# C1G14_VCO_V5.net
KiCad netlist of a schematic drawn in EAGLE
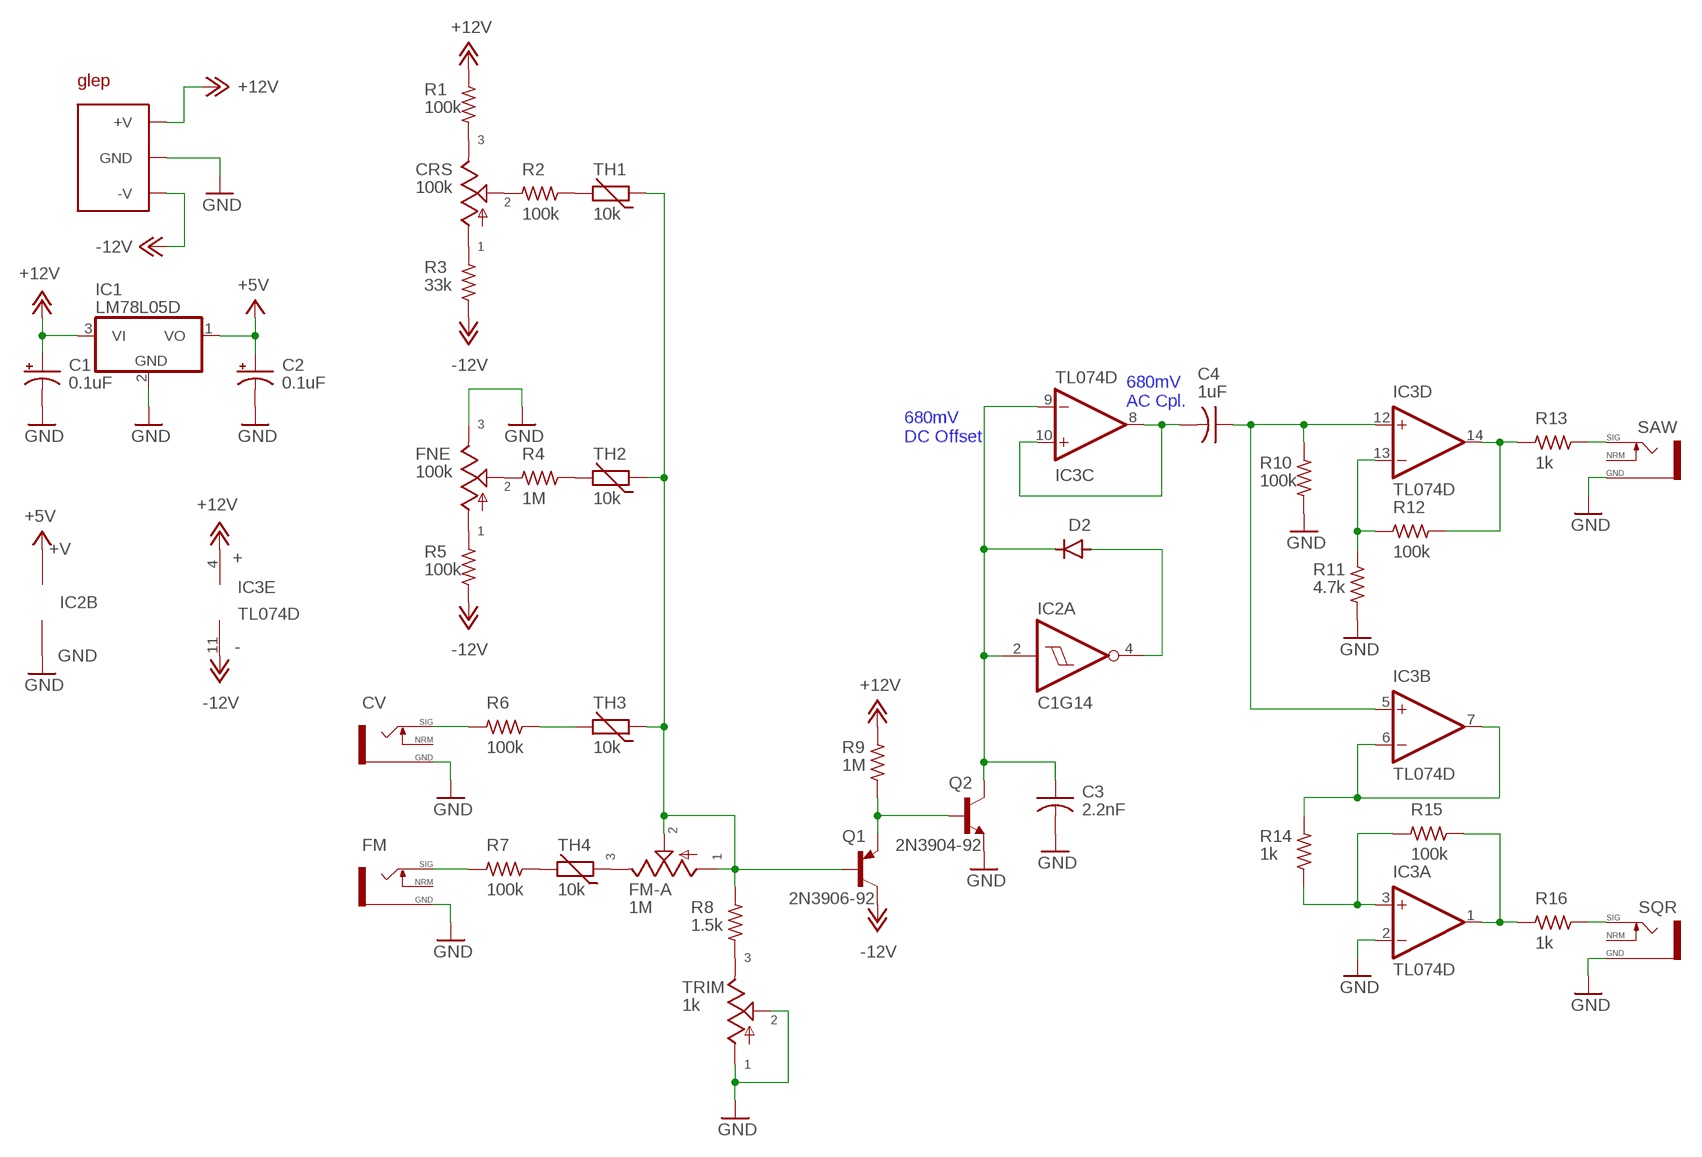
[diagram p0: schematic, sheet 1]

(export (version "E")
  (design (tool "Eeschema 10.0.6"))
  (components
    (comp (ref "C1")
      (value "0.1uF")
      (footprint "eagle-import:E025")
      (libsource (lib "eagle-import") (part "CPOL-E025"))
    )
    (comp (ref "C2")
      (value "0.1uF")
      (footprint "eagle-import:E025")
      (libsource (lib "eagle-import") (part "CPOL-E025"))
    )
    (comp (ref "C3")
      (value "2.2nF")
      (footprint "eagle-import:C05")
      (libsource (lib "eagle-import") (part "C-05"))
    )
    (comp (ref "C4")
      (value "1uF")
      (footprint "eagle-import:C05")
      (libsource (lib "eagle-import") (part "C-05"))
    )
    (comp (ref "CRS")
      (value "100k")
      (footprint "eagle-import:HEADER")
      (libsource (lib "eagle-import") (part "PHDR"))
    )
    (comp (ref "CV")
      (value "MONOHDR")
      (footprint "eagle-import:HEADER")
      (libsource (lib "eagle-import") (part "MONOHDR"))
    )
    (comp (ref "D2")
      (value "D-123")
      (footprint "eagle-import:SOD-123")
      (libsource (lib "eagle-import") (part "D-123"))
    )
    (comp (ref "FM")
      (value "MONOHDR")
      (footprint "eagle-import:HEADER")
      (libsource (lib "eagle-import") (part "MONOHDR"))
    )
    (comp (ref "FM-A")
      (value "1M")
      (footprint "eagle-import:HEADER")
      (libsource (lib "eagle-import") (part "PHDR"))
    )
    (comp (ref "FNE")
      (value "100k")
      (footprint "eagle-import:HEADER")
      (libsource (lib "eagle-import") (part "PHDR"))
    )
    (comp (ref "IC1")
      (value "LM78L05D")
      (footprint "eagle-import:LM78LXX")
      (libsource (lib "eagle-import") (part "LM78L05D"))
    )
    (comp (ref "IC2")
      (value "C1G14")
      (footprint "eagle-import:SOT-23-5")
      (libsource (lib "eagle-import") (part "C1G14"))
    )
    (comp (ref "IC3")
      (value "TL074D")
      (footprint "eagle-import:DIL14")
      (libsource (lib "eagle-import") (part "TL074D"))
    )
    (comp (ref "Q1")
      (value "2N3906-92")
      (footprint "eagle-import:TO92")
      (libsource (lib "eagle-import") (part "2N3906-92"))
    )
    (comp (ref "Q2")
      (value "2N3904-92")
      (footprint "eagle-import:TO92")
      (libsource (lib "eagle-import") (part "2N3904-92"))
    )
    (comp (ref "R1")
      (value "100k")
      (footprint "eagle-import:R1206")
      (libsource (lib "eagle-import") (part "R-1206"))
    )
    (comp (ref "R2")
      (value "100k")
      (footprint "eagle-import:R1206")
      (libsource (lib "eagle-import") (part "R-1206"))
    )
    (comp (ref "R3")
      (value "33k")
      (footprint "eagle-import:R1206")
      (libsource (lib "eagle-import") (part "R-1206"))
    )
    (comp (ref "R4")
      (value "1M")
      (footprint "eagle-import:R1206")
      (libsource (lib "eagle-import") (part "R-1206"))
    )
    (comp (ref "R5")
      (value "100k")
      (footprint "eagle-import:R1206")
      (libsource (lib "eagle-import") (part "R-1206"))
    )
    (comp (ref "R6")
      (value "100k")
      (footprint "eagle-import:R1206")
      (libsource (lib "eagle-import") (part "R-1206"))
    )
    (comp (ref "R7")
      (value "100k")
      (footprint "eagle-import:R1206")
      (libsource (lib "eagle-import") (part "R-1206"))
    )
    (comp (ref "R8")
      (value "1.5k")
      (footprint "eagle-import:R1206")
      (libsource (lib "eagle-import") (part "R-1206"))
    )
    (comp (ref "R9")
      (value "1M")
      (footprint "eagle-import:R1206")
      (libsource (lib "eagle-import") (part "R-1206"))
    )
    (comp (ref "R10")
      (value "100k")
      (footprint "eagle-import:R1206")
      (libsource (lib "eagle-import") (part "R-1206"))
    )
    (comp (ref "R11")
      (value "4.7k")
      (footprint "eagle-import:R1206")
      (libsource (lib "eagle-import") (part "R-1206"))
    )
    (comp (ref "R12")
      (value "100k")
      (footprint "eagle-import:R1206")
      (libsource (lib "eagle-import") (part "R-1206"))
    )
    (comp (ref "R13")
      (value "1k")
      (footprint "eagle-import:R1206")
      (libsource (lib "eagle-import") (part "R-1206"))
    )
    (comp (ref "R14")
      (value "1k")
      (footprint "eagle-import:R1206")
      (libsource (lib "eagle-import") (part "R-1206"))
    )
    (comp (ref "R15")
      (value "100k")
      (footprint "eagle-import:R1206")
      (libsource (lib "eagle-import") (part "R-1206"))
    )
    (comp (ref "R16")
      (value "1k")
      (footprint "eagle-import:R1206")
      (libsource (lib "eagle-import") (part "R-1206"))
    )
    (comp (ref "SAW")
      (value "MONOHDR")
      (footprint "eagle-import:HEADER")
      (libsource (lib "eagle-import") (part "MONOHDR"))
    )
    (comp (ref "SQR")
      (value "MONOHDR")
      (footprint "eagle-import:HEADER")
      (libsource (lib "eagle-import") (part "MONOHDR"))
    )
    (comp (ref "TH1")
      (value "10k")
      (footprint "eagle-import:TH025")
      (libsource (lib "eagle-import") (part "TH-025"))
    )
    (comp (ref "TH2")
      (value "10k")
      (footprint "eagle-import:TH025")
      (libsource (lib "eagle-import") (part "TH-025"))
    )
    (comp (ref "TH3")
      (value "10k")
      (footprint "eagle-import:TH025")
      (libsource (lib "eagle-import") (part "TH-025"))
    )
    (comp (ref "TH4")
      (value "10k")
      (footprint "eagle-import:TH025")
      (libsource (lib "eagle-import") (part "TH-025"))
    )
    (comp (ref "TRIM")
      (value "1k")
      (footprint "eagle-import:HEADER")
      (libsource (lib "eagle-import") (part "PHDR"))
    )
    (comp (ref "U$1")
      (value "10PIN-PWR")
      (footprint "eagle-import:10PIN-HEADER")
      (libsource (lib "eagle-import") (part "10PIN-PWR"))
    )
    (comp (ref "U$2")
      (value "GLEP")
      (footprint "eagle-import:GLEP")
      (libsource (lib "eagle-import") (part "GLEP"))
    )
  )
  (nets
    (net (code "1") (name "+5V") (class "Default")
      (node (ref "C2") (pin "+") (pinfunction "+_+") (pintype "passive"))
      (node (ref "IC1") (pin "1") (pinfunction "VO_1") (pintype "passive"))
      (node (ref "IC2") (pin "5") (pinfunction "V+_5") (pintype "power_in"))
    )
    (net (code "2") (name "+12V") (class "Default")
      (node (ref "C1") (pin "+") (pinfunction "+_+") (pintype "passive"))
      (node (ref "IC1") (pin "3") (pinfunction "VI_3") (pintype "input"))
      (node (ref "IC3") (pin "4") (pinfunction "V+_4") (pintype "power_in"))
      (node (ref "R1") (pin "2") (pinfunction "2_2") (pintype "passive"))
      (node (ref "R9") (pin "2") (pinfunction "2_2") (pintype "passive"))
      (node (ref "U$1") (pin "10") (pinfunction "+V_10") (pintype "bidirectional"))
      (node (ref "U$1") (pin "9") (pinfunction "+V_9") (pintype "bidirectional"))
    )
    (net (code "3") (name "-12V") (class "Default")
      (node (ref "IC3") (pin "11") (pinfunction "V-_11") (pintype "power_in"))
      (node (ref "Q1") (pin "3") (pinfunction "C_3") (pintype "passive"))
      (node (ref "R3") (pin "1") (pinfunction "1_1") (pintype "passive"))
      (node (ref "R5") (pin "1") (pinfunction "1_1") (pintype "passive"))
      (node (ref "U$1") (pin "1") (pinfunction "-V_1") (pintype "bidirectional"))
      (node (ref "U$1") (pin "2") (pinfunction "-V_2") (pintype "bidirectional"))
    )
    (net (code "4") (name "GND") (class "Default")
      (node (ref "C1") (pin "-") (pinfunction "-_-") (pintype "passive"))
      (node (ref "C2") (pin "-") (pinfunction "-_-") (pintype "passive"))
      (node (ref "C3") (pin "2") (pinfunction "2_2") (pintype "passive"))
      (node (ref "CV") (pin "GND") (pinfunction "SLEEVE-GND_GND") (pintype "passive"))
      (node (ref "FM") (pin "GND") (pinfunction "SLEEVE-GND_GND") (pintype "passive"))
      (node (ref "FNE") (pin "3") (pinfunction "3_3") (pintype "passive"))
      (node (ref "IC1") (pin "2") (pinfunction "GND_2") (pintype "passive"))
      (node (ref "IC2") (pin "3") (pinfunction "GND_3") (pintype "passive"))
      (node (ref "IC3") (pin "2") (pinfunction "INVERTING(-)_2") (pintype "input"))
      (node (ref "Q2") (pin "1") (pinfunction "E_1") (pintype "passive"))
      (node (ref "R10") (pin "1") (pinfunction "1_1") (pintype "passive"))
      (node (ref "R11") (pin "1") (pinfunction "1_1") (pintype "passive"))
      (node (ref "SAW") (pin "GND") (pinfunction "SLEEVE-GND_GND") (pintype "passive"))
      (node (ref "SQR") (pin "GND") (pinfunction "SLEEVE-GND_GND") (pintype "passive"))
      (node (ref "TRIM") (pin "1") (pinfunction "1_1") (pintype "passive"))
      (node (ref "TRIM") (pin "2") (pinfunction "2_2") (pintype "passive"))
      (node (ref "U$1") (pin "3") (pinfunction "GND_3") (pintype "bidirectional"))
      (node (ref "U$1") (pin "4") (pinfunction "GND_4") (pintype "bidirectional"))
      (node (ref "U$1") (pin "5") (pinfunction "GND_5") (pintype "bidirectional"))
      (node (ref "U$1") (pin "6") (pinfunction "GND_6") (pintype "bidirectional"))
      (node (ref "U$1") (pin "7") (pinfunction "GND_7") (pintype "bidirectional"))
      (node (ref "U$1") (pin "8") (pinfunction "GND_8") (pintype "bidirectional"))
    )
    (net (code "5") (name "Net-(CRS-Pad1)") (class "Default")
      (node (ref "CRS") (pin "1") (pinfunction "1_1") (pintype "passive"))
      (node (ref "R3") (pin "2") (pinfunction "2_2") (pintype "passive"))
    )
    (net (code "6") (name "Net-(CRS-Pad2)") (class "Default")
      (node (ref "CRS") (pin "2") (pinfunction "2_2") (pintype "passive"))
      (node (ref "R2") (pin "1") (pinfunction "1_1") (pintype "passive"))
    )
    (net (code "7") (name "Net-(CRS-Pad3)") (class "Default")
      (node (ref "CRS") (pin "3") (pinfunction "3_3") (pintype "passive"))
      (node (ref "R1") (pin "1") (pinfunction "1_1") (pintype "passive"))
    )
    (net (code "8") (name "Net-(CV-PadTIP-SIG)") (class "Default")
      (node (ref "CV") (pin "TIP-SIG") (pinfunction "TIP-SIG_TIP-SIG") (pintype "passive"))
      (node (ref "R6") (pin "1") (pinfunction "1_1") (pintype "passive"))
    )
    (net (code "9") (name "Net-(FM-A-Pad3)") (class "Default")
      (node (ref "FM-A") (pin "3") (pinfunction "3_3") (pintype "passive"))
      (node (ref "TH4") (pin "1") (pinfunction "1_1") (pintype "passive"))
    )
    (net (code "10") (name "Net-(FM-PadTIP-SIG)") (class "Default")
      (node (ref "FM") (pin "TIP-SIG") (pinfunction "TIP-SIG_TIP-SIG") (pintype "passive"))
      (node (ref "R7") (pin "1") (pinfunction "1_1") (pintype "passive"))
    )
    (net (code "11") (name "Net-(FNE-Pad1)") (class "Default")
      (node (ref "FNE") (pin "1") (pinfunction "1_1") (pintype "passive"))
      (node (ref "R5") (pin "2") (pinfunction "2_2") (pintype "passive"))
    )
    (net (code "12") (name "Net-(FNE-Pad2)") (class "Default")
      (node (ref "FNE") (pin "2") (pinfunction "2_2") (pintype "passive"))
      (node (ref "R4") (pin "1") (pinfunction "1_1") (pintype "passive"))
    )
    (net (code "13") (name "Net-(IC2A-A)") (class "Default")
      (node (ref "C3") (pin "1") (pinfunction "1_1") (pintype "passive"))
      (node (ref "D2") (pin "C") (pinfunction "C_C") (pintype "passive"))
      (node (ref "IC2") (pin "2") (pinfunction "A_2") (pintype "input"))
      (node (ref "IC3") (pin "9") (pinfunction "INVERTING(-)_9") (pintype "input"))
      (node (ref "Q2") (pin "3") (pinfunction "C_3") (pintype "passive"))
    )
    (net (code "14") (name "Net-(IC2A-Y)") (class "Default")
      (node (ref "D2") (pin "A") (pinfunction "A_A") (pintype "passive"))
      (node (ref "IC2") (pin "4") (pinfunction "Y_4") (pintype "output"))
    )
    (net (code "15") (name "Net-(IC3A-NON-INVERTING(+))") (class "Default")
      (node (ref "IC3") (pin "3") (pinfunction "NON-INVERTING(+)_3") (pintype "input"))
      (node (ref "R14") (pin "1") (pinfunction "1_1") (pintype "passive"))
      (node (ref "R15") (pin "1") (pinfunction "1_1") (pintype "passive"))
    )
    (net (code "16") (name "Net-(IC3A-OUT)") (class "Default")
      (node (ref "IC3") (pin "1") (pinfunction "OUT_1") (pintype "output"))
      (node (ref "R15") (pin "2") (pinfunction "2_2") (pintype "passive"))
      (node (ref "R16") (pin "1") (pinfunction "1_1") (pintype "passive"))
    )
    (net (code "17") (name "Net-(IC3B-INVERTING(-))") (class "Default")
      (node (ref "IC3") (pin "6") (pinfunction "INVERTING(-)_6") (pintype "input"))
      (node (ref "IC3") (pin "7") (pinfunction "OUT_7") (pintype "output"))
      (node (ref "R14") (pin "2") (pinfunction "2_2") (pintype "passive"))
    )
    (net (code "18") (name "Net-(IC3B-NON-INVERTING(+))") (class "Default")
      (node (ref "C4") (pin "1") (pinfunction "1_1") (pintype "passive"))
      (node (ref "IC3") (pin "12") (pinfunction "NON-INVERTING(+)_12") (pintype "input"))
      (node (ref "IC3") (pin "5") (pinfunction "NON-INVERTING(+)_5") (pintype "input"))
      (node (ref "R10") (pin "2") (pinfunction "2_2") (pintype "passive"))
    )
    (net (code "19") (name "Net-(IC3C-NON-INVERTING(+))") (class "Default")
      (node (ref "C4") (pin "2") (pinfunction "2_2") (pintype "passive"))
      (node (ref "IC3") (pin "10") (pinfunction "NON-INVERTING(+)_10") (pintype "input"))
      (node (ref "IC3") (pin "8") (pinfunction "OUT_8") (pintype "output"))
    )
    (net (code "20") (name "Net-(IC3D-INVERTING(-))") (class "Default")
      (node (ref "IC3") (pin "13") (pinfunction "INVERTING(-)_13") (pintype "input"))
      (node (ref "R11") (pin "2") (pinfunction "2_2") (pintype "passive"))
      (node (ref "R12") (pin "1") (pinfunction "1_1") (pintype "passive"))
    )
    (net (code "21") (name "Net-(IC3D-OUT)") (class "Default")
      (node (ref "IC3") (pin "14") (pinfunction "OUT_14") (pintype "output"))
      (node (ref "R12") (pin "2") (pinfunction "2_2") (pintype "passive"))
      (node (ref "R13") (pin "1") (pinfunction "1_1") (pintype "passive"))
    )
    (net (code "22") (name "Net-(Q1-B)") (class "Default")
      (node (ref "FM-A") (pin "1") (pinfunction "1_1") (pintype "passive"))
      (node (ref "FM-A") (pin "2") (pinfunction "2_2") (pintype "passive"))
      (node (ref "Q1") (pin "2") (pinfunction "B_2") (pintype "passive"))
      (node (ref "R8") (pin "2") (pinfunction "2_2") (pintype "passive"))
      (node (ref "TH1") (pin "1") (pinfunction "1_1") (pintype "passive"))
      (node (ref "TH2") (pin "1") (pinfunction "1_1") (pintype "passive"))
      (node (ref "TH3") (pin "1") (pinfunction "1_1") (pintype "passive"))
    )
    (net (code "23") (name "Net-(Q1-E)") (class "Default")
      (node (ref "Q1") (pin "1") (pinfunction "E_1") (pintype "passive"))
      (node (ref "Q2") (pin "2") (pinfunction "B_2") (pintype "passive"))
      (node (ref "R9") (pin "1") (pinfunction "1_1") (pintype "passive"))
    )
    (net (code "24") (name "Net-(R2-Pad2)") (class "Default")
      (node (ref "R2") (pin "2") (pinfunction "2_2") (pintype "passive"))
      (node (ref "TH1") (pin "2") (pinfunction "2_2") (pintype "passive"))
    )
    (net (code "25") (name "Net-(R4-Pad2)") (class "Default")
      (node (ref "R4") (pin "2") (pinfunction "2_2") (pintype "passive"))
      (node (ref "TH2") (pin "2") (pinfunction "2_2") (pintype "passive"))
    )
    (net (code "26") (name "Net-(R6-Pad2)") (class "Default")
      (node (ref "R6") (pin "2") (pinfunction "2_2") (pintype "passive"))
      (node (ref "TH3") (pin "2") (pinfunction "2_2") (pintype "passive"))
    )
    (net (code "27") (name "Net-(R7-Pad2)") (class "Default")
      (node (ref "R7") (pin "2") (pinfunction "2_2") (pintype "passive"))
      (node (ref "TH4") (pin "2") (pinfunction "2_2") (pintype "passive"))
    )
    (net (code "28") (name "Net-(R8-Pad1)") (class "Default")
      (node (ref "R8") (pin "1") (pinfunction "1_1") (pintype "passive"))
      (node (ref "TRIM") (pin "3") (pinfunction "3_3") (pintype "passive"))
    )
    (net (code "29") (name "Net-(R13-Pad2)") (class "Default")
      (node (ref "R13") (pin "2") (pinfunction "2_2") (pintype "passive"))
      (node (ref "SAW") (pin "TIP-SIG") (pinfunction "TIP-SIG_TIP-SIG") (pintype "passive"))
    )
    (net (code "30") (name "Net-(R16-Pad2)") (class "Default")
      (node (ref "R16") (pin "2") (pinfunction "2_2") (pintype "passive"))
      (node (ref "SQR") (pin "TIP-SIG") (pinfunction "TIP-SIG_TIP-SIG") (pintype "passive"))
    )
    (net (code "31") (name "unconnected-(CV-SWITCH-NORM-PadNORM)") (class "Default")
      (node (ref "CV") (pin "NORM") (pinfunction "SWITCH-NORM_NORM") (pintype "passive"))
    )
    (net (code "32") (name "unconnected-(FM-SWITCH-NORM-PadNORM)") (class "Default")
      (node (ref "FM") (pin "NORM") (pinfunction "SWITCH-NORM_NORM") (pintype "passive"))
    )
    (net (code "33") (name "unconnected-(SAW-SWITCH-NORM-PadNORM)") (class "Default")
      (node (ref "SAW") (pin "NORM") (pinfunction "SWITCH-NORM_NORM") (pintype "passive"))
    )
    (net (code "34") (name "unconnected-(SQR-SWITCH-NORM-PadNORM)") (class "Default")
      (node (ref "SQR") (pin "NORM") (pinfunction "SWITCH-NORM_NORM") (pintype "passive"))
    )
  )
)
